# robo1.net
KiCad netlist of a schematic drawn in EAGLE
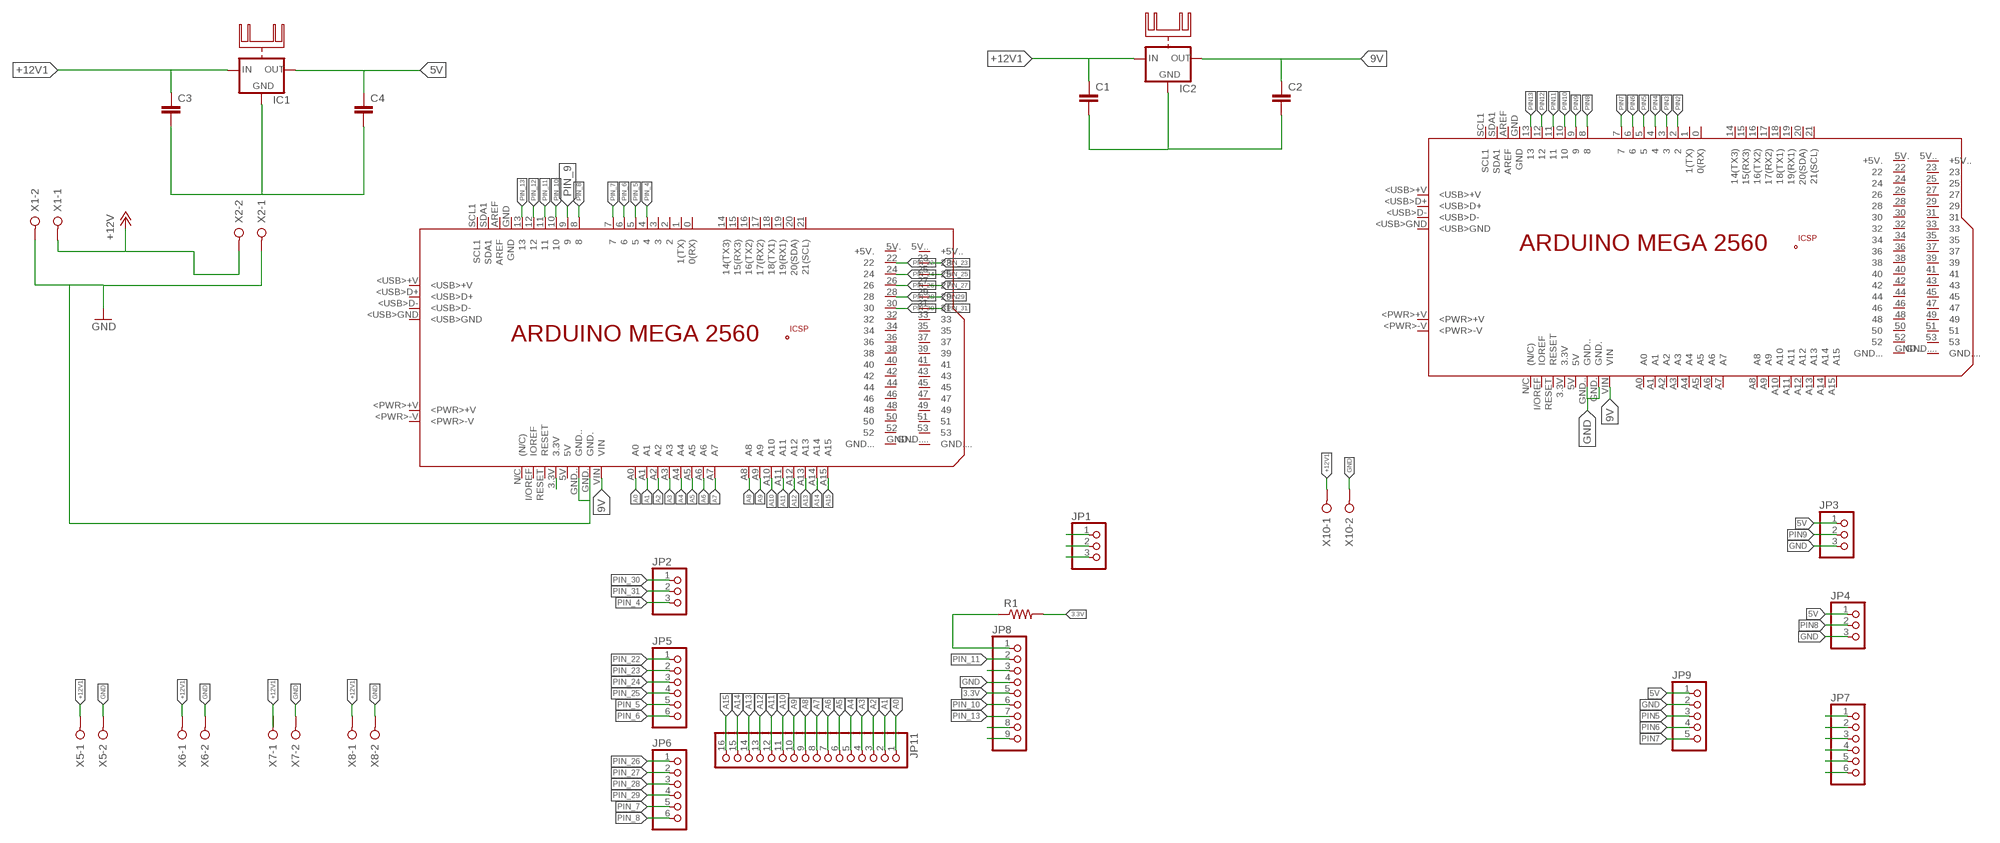
[diagram p0: schematic, sheet 1]

(export (version "E")
  (design (tool "Eeschema 10.0.6"))
  (components
    (comp (ref "C1")
      (value "C5/2.5")
      (footprint "eagle-import:C5B2.5")
      (libsource (lib "eagle-import") (part "C5/2.5"))
    )
    (comp (ref "C2")
      (value "C5/2.5")
      (footprint "eagle-import:C5B2.5")
      (libsource (lib "eagle-import") (part "C5/2.5"))
    )
    (comp (ref "C3")
      (value "C5/2.5")
      (footprint "eagle-import:C5B2.5")
      (libsource (lib "eagle-import") (part "C5/2.5"))
    )
    (comp (ref "C4")
      (value "C5/2.5")
      (footprint "eagle-import:C5B2.5")
      (libsource (lib "eagle-import") (part "C5/2.5"))
    )
    (comp (ref "IC1")
      (value "78XXH")
      (footprint "eagle-import:78XXH")
      (libsource (lib "eagle-import") (part "78XXH"))
    )
    (comp (ref "IC2")
      (value "78XXH")
      (footprint "eagle-import:78XXH")
      (libsource (lib "eagle-import") (part "78XXH"))
    )
    (comp (ref "JP1")
      (value "PINHD-1X3")
      (footprint "eagle-import:1X03")
      (libsource (lib "eagle-import") (part "PINHD-1X3"))
    )
    (comp (ref "JP2")
      (value "PINHD-1X3")
      (footprint "eagle-import:1X03")
      (libsource (lib "eagle-import") (part "PINHD-1X3"))
    )
    (comp (ref "JP3")
      (value "PINHD-1X3")
      (footprint "eagle-import:1X03")
      (libsource (lib "eagle-import") (part "PINHD-1X3"))
    )
    (comp (ref "JP4")
      (value "PINHD-1X3")
      (footprint "eagle-import:1X03")
      (libsource (lib "eagle-import") (part "PINHD-1X3"))
    )
    (comp (ref "JP5")
      (value "PINHD-1X6")
      (footprint "eagle-import:1X06")
      (libsource (lib "eagle-import") (part "PINHD-1X6"))
    )
    (comp (ref "JP6")
      (value "PINHD-1X6")
      (footprint "eagle-import:1X06")
      (libsource (lib "eagle-import") (part "PINHD-1X6"))
    )
    (comp (ref "JP7")
      (value "PINHD-1X6")
      (footprint "eagle-import:1X06")
      (libsource (lib "eagle-import") (part "PINHD-1X6"))
    )
    (comp (ref "JP8")
      (value "PINHD-1X9")
      (footprint "eagle-import:1X09")
      (libsource (lib "eagle-import") (part "PINHD-1X9"))
    )
    (comp (ref "JP9")
      (value "PINHD-1X5")
      (footprint "eagle-import:1X05")
      (libsource (lib "eagle-import") (part "PINHD-1X5"))
    )
    (comp (ref "JP11")
      (value "PINHD-1X16")
      (footprint "eagle-import:1X16")
      (libsource (lib "eagle-import") (part "PINHD-1X16"))
    )
    (comp (ref "MEGA1")
      (value "ARDUINO_MEGA2560")
      (footprint "eagle-import:ARDUINO_MEGA2560")
      (libsource (lib "eagle-import") (part "ARDUINO_MEGA2560"))
    )
    (comp (ref "MEGA2")
      (value "ARDUINO_MEGA2560")
      (footprint "eagle-import:ARDUINO_MEGA2560")
      (libsource (lib "eagle-import") (part "ARDUINO_MEGA2560"))
    )
    (comp (ref "R1")
      (value "R-US_0207/10")
      (footprint "eagle-import:0207_10")
      (libsource (lib "eagle-import") (part "R-US_0207/10"))
    )
    (comp (ref "X1")
      (value "W237-02P")
      (footprint "eagle-import:W237-132")
      (libsource (lib "eagle-import") (part "W237-02P"))
    )
    (comp (ref "X2")
      (value "W237-02P")
      (footprint "eagle-import:W237-132")
      (libsource (lib "eagle-import") (part "W237-02P"))
    )
    (comp (ref "X5")
      (value "W237-02P")
      (footprint "eagle-import:W237-132")
      (libsource (lib "eagle-import") (part "W237-02P"))
    )
    (comp (ref "X6")
      (value "W237-02P")
      (footprint "eagle-import:W237-132")
      (libsource (lib "eagle-import") (part "W237-02P"))
    )
    (comp (ref "X7")
      (value "W237-02P")
      (footprint "eagle-import:W237-132")
      (libsource (lib "eagle-import") (part "W237-02P"))
    )
    (comp (ref "X8")
      (value "W237-02P")
      (footprint "eagle-import:W237-132")
      (libsource (lib "eagle-import") (part "W237-02P"))
    )
    (comp (ref "X10")
      (value "W237-02P")
      (footprint "eagle-import:W237-132")
      (libsource (lib "eagle-import") (part "W237-02P"))
    )
  )
  (nets
    (net (code "1") (name "+12V") (class "Default")
      (node (ref "X1") (pin "1") (pinfunction "KL_1") (pintype "passive"))
      (node (ref "X2") (pin "2") (pinfunction "KL_2") (pintype "passive"))
    )
    (net (code "2") (name "+12V1") (class "Default")
      (node (ref "C1") (pin "1") (pinfunction "1_1") (pintype "passive"))
      (node (ref "C3") (pin "1") (pinfunction "1_1") (pintype "passive"))
      (node (ref "IC1") (pin "IN") (pinfunction "IN_IN") (pintype "input"))
      (node (ref "IC2") (pin "IN") (pinfunction "IN_IN") (pintype "input"))
      (node (ref "X10") (pin "1") (pinfunction "KL_1") (pintype "passive"))
      (node (ref "X5") (pin "1") (pinfunction "KL_1") (pintype "passive"))
      (node (ref "X6") (pin "1") (pinfunction "KL_1") (pintype "passive"))
      (node (ref "X8") (pin "1") (pinfunction "KL_1") (pintype "passive"))
    )
    (net (code "3") (name "3.3V") (class "Default")
      (node (ref "JP8") (pin "5") (pinfunction "5_5") (pintype "passive"))
      (node (ref "MEGA1") (pin "3.3V") (pinfunction "3.3V_3.3V") (pintype "bidirectional"))
      (node (ref "R1") (pin "2") (pinfunction "2_2") (pintype "passive"))
    )
    (net (code "4") (name "5V") (class "Default")
      (node (ref "C4") (pin "1") (pinfunction "1_1") (pintype "passive"))
      (node (ref "IC1") (pin "OUT") (pinfunction "OUT_OUT") (pintype "passive"))
      (node (ref "JP3") (pin "1") (pinfunction "1_1") (pintype "passive"))
      (node (ref "JP4") (pin "1") (pinfunction "1_1") (pintype "passive"))
      (node (ref "JP9") (pin "1") (pinfunction "1_1") (pintype "passive"))
    )
    (net (code "5") (name "9V") (class "Default")
      (node (ref "C2") (pin "1") (pinfunction "1_1") (pintype "passive"))
      (node (ref "IC2") (pin "OUT") (pinfunction "OUT_OUT") (pintype "passive"))
      (node (ref "MEGA1") (pin "VIN") (pinfunction "VIN_VIN") (pintype "bidirectional"))
      (node (ref "MEGA2") (pin "VIN") (pinfunction "VIN_VIN") (pintype "bidirectional"))
    )
    (net (code "6") (name "A0") (class "Default")
      (node (ref "JP11") (pin "1") (pinfunction "1_1") (pintype "passive"))
      (node (ref "MEGA1") (pin "A0") (pinfunction "A0_A0") (pintype "bidirectional"))
    )
    (net (code "7") (name "A1") (class "Default")
      (node (ref "JP11") (pin "2") (pinfunction "2_2") (pintype "passive"))
      (node (ref "MEGA1") (pin "A1") (pinfunction "A1_A1") (pintype "bidirectional"))
    )
    (net (code "8") (name "A2") (class "Default")
      (node (ref "JP11") (pin "3") (pinfunction "3_3") (pintype "passive"))
      (node (ref "MEGA1") (pin "A2") (pinfunction "A2_A2") (pintype "bidirectional"))
    )
    (net (code "9") (name "A3") (class "Default")
      (node (ref "JP11") (pin "4") (pinfunction "4_4") (pintype "passive"))
      (node (ref "MEGA1") (pin "A3") (pinfunction "A3_A3") (pintype "bidirectional"))
    )
    (net (code "10") (name "A4") (class "Default")
      (node (ref "JP11") (pin "5") (pinfunction "5_5") (pintype "passive"))
      (node (ref "MEGA1") (pin "A4") (pinfunction "A4_A4") (pintype "bidirectional"))
    )
    (net (code "11") (name "A5") (class "Default")
      (node (ref "JP11") (pin "6") (pinfunction "6_6") (pintype "passive"))
      (node (ref "MEGA1") (pin "A5") (pinfunction "A5_A5") (pintype "bidirectional"))
    )
    (net (code "12") (name "A6") (class "Default")
      (node (ref "JP11") (pin "7") (pinfunction "7_7") (pintype "passive"))
      (node (ref "MEGA1") (pin "A6") (pinfunction "A6_A6") (pintype "bidirectional"))
    )
    (net (code "13") (name "A7") (class "Default")
      (node (ref "JP11") (pin "8") (pinfunction "8_8") (pintype "passive"))
      (node (ref "MEGA1") (pin "A7") (pinfunction "A7_A7") (pintype "bidirectional"))
    )
    (net (code "14") (name "A8") (class "Default")
      (node (ref "JP11") (pin "9") (pinfunction "9_9") (pintype "passive"))
      (node (ref "MEGA1") (pin "A8") (pinfunction "A8_A8") (pintype "bidirectional"))
    )
    (net (code "15") (name "A9") (class "Default")
      (node (ref "JP11") (pin "10") (pinfunction "10_10") (pintype "passive"))
      (node (ref "MEGA1") (pin "A9") (pinfunction "A9_A9") (pintype "bidirectional"))
    )
    (net (code "16") (name "A10") (class "Default")
      (node (ref "JP11") (pin "11") (pinfunction "11_11") (pintype "passive"))
      (node (ref "MEGA1") (pin "A10") (pinfunction "A10_A10") (pintype "bidirectional"))
    )
    (net (code "17") (name "A11") (class "Default")
      (node (ref "JP11") (pin "12") (pinfunction "12_12") (pintype "passive"))
      (node (ref "MEGA1") (pin "A11") (pinfunction "A11_A11") (pintype "bidirectional"))
    )
    (net (code "18") (name "A12") (class "Default")
      (node (ref "JP11") (pin "13") (pinfunction "13_13") (pintype "passive"))
      (node (ref "MEGA1") (pin "A12") (pinfunction "A12_A12") (pintype "bidirectional"))
    )
    (net (code "19") (name "A13") (class "Default")
      (node (ref "JP11") (pin "14") (pinfunction "14_14") (pintype "passive"))
      (node (ref "MEGA1") (pin "A13") (pinfunction "A13_A13") (pintype "bidirectional"))
    )
    (net (code "20") (name "A14") (class "Default")
      (node (ref "JP11") (pin "15") (pinfunction "15_15") (pintype "passive"))
      (node (ref "MEGA1") (pin "A14") (pinfunction "A14_A14") (pintype "bidirectional"))
    )
    (net (code "21") (name "A15") (class "Default")
      (node (ref "JP11") (pin "16") (pinfunction "16_16") (pintype "passive"))
      (node (ref "MEGA1") (pin "A15") (pinfunction "A15_A15") (pintype "bidirectional"))
    )
    (net (code "22") (name "GND") (class "Default")
      (node (ref "C1") (pin "2") (pinfunction "2_2") (pintype "passive"))
      (node (ref "C2") (pin "2") (pinfunction "2_2") (pintype "passive"))
      (node (ref "C3") (pin "2") (pinfunction "2_2") (pintype "passive"))
      (node (ref "C4") (pin "2") (pinfunction "2_2") (pintype "passive"))
      (node (ref "IC1") (pin "GND") (pinfunction "GND_GND") (pintype "input"))
      (node (ref "IC2") (pin "GND") (pinfunction "GND_GND") (pintype "input"))
      (node (ref "JP1") (pin "1") (pinfunction "1_1") (pintype "passive"))
      (node (ref "JP3") (pin "3") (pinfunction "3_3") (pintype "passive"))
      (node (ref "JP4") (pin "3") (pinfunction "3_3") (pintype "passive"))
      (node (ref "JP8") (pin "4") (pinfunction "4_4") (pintype "passive"))
      (node (ref "JP9") (pin "2") (pinfunction "2_2") (pintype "passive"))
      (node (ref "MEGA1") (pin "GND.") (pinfunction "GND._GND.") (pintype "bidirectional"))
      (node (ref "MEGA1") (pin "GND..") (pinfunction "GND.._GND..") (pintype "bidirectional"))
      (node (ref "MEGA2") (pin "GND.") (pinfunction "GND._GND.") (pintype "bidirectional"))
      (node (ref "MEGA2") (pin "GND..") (pinfunction "GND.._GND..") (pintype "bidirectional"))
      (node (ref "X1") (pin "2") (pinfunction "KL_2") (pintype "passive"))
      (node (ref "X10") (pin "2") (pinfunction "KL_2") (pintype "passive"))
      (node (ref "X2") (pin "1") (pinfunction "KL_1") (pintype "passive"))
      (node (ref "X5") (pin "2") (pinfunction "KL_2") (pintype "passive"))
      (node (ref "X6") (pin "2") (pinfunction "KL_2") (pintype "passive"))
      (node (ref "X7") (pin "2") (pinfunction "KL_2") (pintype "passive"))
      (node (ref "X8") (pin "2") (pinfunction "KL_2") (pintype "passive"))
    )
    (net (code "23") (name "PIN2") (class "Default")
      (node (ref "JP7") (pin "1") (pinfunction "1_1") (pintype "passive"))
      (node (ref "MEGA2") (pin "2") (pinfunction "2_2") (pintype "bidirectional"))
    )
    (net (code "24") (name "PIN3") (class "Default")
      (node (ref "JP7") (pin "2") (pinfunction "2_2") (pintype "passive"))
      (node (ref "MEGA2") (pin "3") (pinfunction "3_3") (pintype "bidirectional"))
    )
    (net (code "25") (name "PIN4") (class "Default")
      (node (ref "MEGA2") (pin "4") (pinfunction "4_4") (pintype "bidirectional"))
    )
    (net (code "26") (name "PIN5") (class "Default")
      (node (ref "JP9") (pin "3") (pinfunction "3_3") (pintype "passive"))
      (node (ref "MEGA2") (pin "5") (pinfunction "5_5") (pintype "bidirectional"))
    )
    (net (code "27") (name "PIN6") (class "Default")
      (node (ref "JP9") (pin "4") (pinfunction "4_4") (pintype "passive"))
      (node (ref "MEGA2") (pin "6") (pinfunction "6_6") (pintype "bidirectional"))
    )
    (net (code "28") (name "PIN7") (class "Default")
      (node (ref "JP9") (pin "5") (pinfunction "5_5") (pintype "passive"))
      (node (ref "MEGA2") (pin "7") (pinfunction "7_7") (pintype "bidirectional"))
    )
    (net (code "29") (name "PIN8") (class "Default")
      (node (ref "JP4") (pin "2") (pinfunction "2_2") (pintype "passive"))
      (node (ref "MEGA2") (pin "8") (pinfunction "8_8") (pintype "bidirectional"))
    )
    (net (code "30") (name "PIN9") (class "Default")
      (node (ref "JP3") (pin "2") (pinfunction "2_2") (pintype "passive"))
      (node (ref "MEGA2") (pin "9") (pinfunction "9_9") (pintype "bidirectional"))
    )
    (net (code "31") (name "PIN10") (class "Default")
      (node (ref "JP7") (pin "3") (pinfunction "3_3") (pintype "passive"))
      (node (ref "MEGA2") (pin "10") (pinfunction "10_10") (pintype "bidirectional"))
    )
    (net (code "32") (name "PIN11") (class "Default")
      (node (ref "JP7") (pin "4") (pinfunction "4_4") (pintype "passive"))
      (node (ref "MEGA2") (pin "11") (pinfunction "11_11") (pintype "bidirectional"))
    )
    (net (code "33") (name "PIN12") (class "Default")
      (node (ref "JP7") (pin "5") (pinfunction "5_5") (pintype "passive"))
      (node (ref "MEGA2") (pin "12") (pinfunction "12_12") (pintype "bidirectional"))
    )
    (net (code "34") (name "PIN13") (class "Default")
      (node (ref "JP7") (pin "6") (pinfunction "6_6") (pintype "passive"))
      (node (ref "MEGA2") (pin "13") (pinfunction "13_13") (pintype "bidirectional"))
    )
    (net (code "36") (name "PIN_4") (class "Default")
      (node (ref "JP2") (pin "3") (pinfunction "3_3") (pintype "passive"))
      (node (ref "MEGA1") (pin "4") (pinfunction "4_4") (pintype "bidirectional"))
    )
    (net (code "37") (name "PIN_5") (class "Default")
      (node (ref "JP5") (pin "5") (pinfunction "5_5") (pintype "passive"))
      (node (ref "MEGA1") (pin "5") (pinfunction "5_5") (pintype "bidirectional"))
    )
    (net (code "38") (name "PIN_6") (class "Default")
      (node (ref "JP5") (pin "6") (pinfunction "6_6") (pintype "passive"))
      (node (ref "MEGA1") (pin "6") (pinfunction "6_6") (pintype "bidirectional"))
    )
    (net (code "39") (name "PIN_7") (class "Default")
      (node (ref "JP6") (pin "5") (pinfunction "5_5") (pintype "passive"))
      (node (ref "MEGA1") (pin "7") (pinfunction "7_7") (pintype "bidirectional"))
    )
    (net (code "40") (name "PIN_8") (class "Default")
      (node (ref "JP6") (pin "6") (pinfunction "6_6") (pintype "passive"))
      (node (ref "MEGA1") (pin "8") (pinfunction "8_8") (pintype "bidirectional"))
    )
    (net (code "41") (name "PIN_9") (class "Default")
      (node (ref "JP1") (pin "3") (pinfunction "3_3") (pintype "passive"))
      (node (ref "MEGA1") (pin "9") (pinfunction "9_9") (pintype "bidirectional"))
    )
    (net (code "42") (name "PIN_10") (class "Default")
      (node (ref "JP8") (pin "6") (pinfunction "6_6") (pintype "passive"))
      (node (ref "MEGA1") (pin "10") (pinfunction "10_10") (pintype "bidirectional"))
    )
    (net (code "43") (name "PIN_11") (class "Default")
      (node (ref "JP8") (pin "2") (pinfunction "2_2") (pintype "passive"))
      (node (ref "MEGA1") (pin "11") (pinfunction "11_11") (pintype "bidirectional"))
    )
    (net (code "44") (name "PIN_12") (class "Default")
      (node (ref "JP8") (pin "1") (pinfunction "1_1") (pintype "passive"))
      (node (ref "MEGA1") (pin "12") (pinfunction "12_12") (pintype "bidirectional"))
      (node (ref "R1") (pin "1") (pinfunction "1_1") (pintype "passive"))
    )
    (net (code "45") (name "PIN_13") (class "Default")
      (node (ref "JP8") (pin "7") (pinfunction "7_7") (pintype "passive"))
      (node (ref "MEGA1") (pin "13") (pinfunction "13_13") (pintype "bidirectional"))
    )
    (net (code "46") (name "PIN_22") (class "Default")
      (node (ref "JP5") (pin "1") (pinfunction "1_1") (pintype "passive"))
      (node (ref "MEGA1") (pin "22") (pinfunction "22_22") (pintype "bidirectional"))
    )
    (net (code "47") (name "PIN_23") (class "Default")
      (node (ref "JP5") (pin "2") (pinfunction "2_2") (pintype "passive"))
    )
    (net (code "48") (name "PIN_24") (class "Default")
      (node (ref "JP5") (pin "3") (pinfunction "3_3") (pintype "passive"))
      (node (ref "MEGA1") (pin "24") (pinfunction "24_24") (pintype "bidirectional"))
    )
    (net (code "49") (name "PIN_25") (class "Default")
      (node (ref "JP5") (pin "4") (pinfunction "4_4") (pintype "passive"))
    )
    (net (code "50") (name "PIN_26") (class "Default")
      (node (ref "JP6") (pin "1") (pinfunction "1_1") (pintype "passive"))
      (node (ref "MEGA1") (pin "26") (pinfunction "26_26") (pintype "bidirectional"))
    )
    (net (code "51") (name "PIN_27") (class "Default")
      (node (ref "JP6") (pin "2") (pinfunction "2_2") (pintype "passive"))
    )
    (net (code "52") (name "PIN_28") (class "Default")
      (node (ref "JP6") (pin "3") (pinfunction "3_3") (pintype "passive"))
      (node (ref "MEGA1") (pin "28") (pinfunction "28_28") (pintype "bidirectional"))
    )
    (net (code "53") (name "PIN_29") (class "Default")
      (node (ref "JP6") (pin "4") (pinfunction "4_4") (pintype "passive"))
    )
    (net (code "54") (name "PIN_30") (class "Default")
      (node (ref "JP2") (pin "1") (pinfunction "1_1") (pintype "passive"))
      (node (ref "MEGA1") (pin "30") (pinfunction "30_30") (pintype "bidirectional"))
    )
    (net (code "55") (name "PIN_31") (class "Default")
      (node (ref "JP2") (pin "2") (pinfunction "2_2") (pintype "passive"))
    )
    (net (code "56") (name "unconnected-(JP1-Pad2)") (class "Default")
      (node (ref "JP1") (pin "2") (pinfunction "2_2") (pintype "passive"))
    )
    (net (code "57") (name "unconnected-(JP8-Pad3)") (class "Default")
      (node (ref "JP8") (pin "3") (pinfunction "3_3") (pintype "passive"))
    )
    (net (code "58") (name "unconnected-(JP8-Pad8)") (class "Default")
      (node (ref "JP8") (pin "8") (pinfunction "8_8") (pintype "passive"))
    )
    (net (code "59") (name "unconnected-(JP8-Pad9)") (class "Default")
      (node (ref "JP8") (pin "9") (pinfunction "9_9") (pintype "passive"))
    )
    (net (code "60") (name "unconnected-(MEGA1-(N{slash}C)-PadN{slash}C)") (class "Default")
      (node (ref "MEGA1") (pin "N/C") (pinfunction "(N/C)_N/C") (pintype "bidirectional"))
    )
    (net (code "61") (name "unconnected-(MEGA1-+5V.-Pad5V.)") (class "Default")
      (node (ref "MEGA1") (pin "5V.") (pinfunction "+5V._5V.") (pintype "bidirectional"))
    )
    (net (code "62") (name "unconnected-(MEGA1-+5V..-Pad5V..)") (class "Default")
      (node (ref "MEGA1") (pin "5V..") (pinfunction "+5V.._5V..") (pintype "bidirectional"))
    )
    (net (code "63") (name "unconnected-(MEGA1-0(RX)-Pad0)") (class "Default")
      (node (ref "MEGA1") (pin "0") (pinfunction "0(RX)_0") (pintype "bidirectional"))
    )
    (net (code "64") (name "unconnected-(MEGA1-1(TX)-Pad1)") (class "Default")
      (node (ref "MEGA1") (pin "1") (pinfunction "1(TX)_1") (pintype "bidirectional"))
    )
    (net (code "65") (name "unconnected-(MEGA1-14(TX3)-Pad14)") (class "Default")
      (node (ref "MEGA1") (pin "14") (pinfunction "14(TX3)_14") (pintype "bidirectional"))
    )
    (net (code "66") (name "unconnected-(MEGA1-15(RX3)-Pad15)") (class "Default")
      (node (ref "MEGA1") (pin "15") (pinfunction "15(RX3)_15") (pintype "bidirectional"))
    )
    (net (code "67") (name "unconnected-(MEGA1-16(TX2)-Pad16)") (class "Default")
      (node (ref "MEGA1") (pin "16") (pinfunction "16(TX2)_16") (pintype "bidirectional"))
    )
    (net (code "68") (name "unconnected-(MEGA1-17(RX2)-Pad17)") (class "Default")
      (node (ref "MEGA1") (pin "17") (pinfunction "17(RX2)_17") (pintype "bidirectional"))
    )
    (net (code "69") (name "unconnected-(MEGA1-18(TX1)-Pad18)") (class "Default")
      (node (ref "MEGA1") (pin "18") (pinfunction "18(TX1)_18") (pintype "bidirectional"))
    )
    (net (code "70") (name "unconnected-(MEGA1-19(RX1)-Pad19)") (class "Default")
      (node (ref "MEGA1") (pin "19") (pinfunction "19(RX1)_19") (pintype "bidirectional"))
    )
    (net (code "71") (name "unconnected-(MEGA1-20(SDA)-Pad20)") (class "Default")
      (node (ref "MEGA1") (pin "20") (pinfunction "20(SDA)_20") (pintype "bidirectional"))
    )
    (net (code "72") (name "unconnected-(MEGA1-21(SCL)-Pad21)") (class "Default")
      (node (ref "MEGA1") (pin "21") (pinfunction "21(SCL)_21") (pintype "bidirectional"))
    )
    (net (code "73") (name "unconnected-(MEGA1-IOREF-PadI{slash}OREF)") (class "Default")
      (node (ref "MEGA1") (pin "I/OREF") (pinfunction "IOREF_I/OREF") (pintype "bidirectional"))
    )
    (net (code "74") (name "unconnected-(MEGA1-Pad+5V_)") (class "Default")
      (node (ref "MEGA1") (pin "+5V_") (pinfunction "+5V__+5V_") (pintype "bidirectional"))
    )
    (net (code "75") (name "unconnected-(MEGA1-Pad2)") (class "Default")
      (node (ref "MEGA1") (pin "2") (pinfunction "2_2") (pintype "bidirectional"))
    )
    (net (code "76") (name "unconnected-(MEGA1-Pad3)") (class "Default")
      (node (ref "MEGA1") (pin "3") (pinfunction "3_3") (pintype "bidirectional"))
    )
    (net (code "77") (name "unconnected-(MEGA1-Pad5V)") (class "Default")
      (node (ref "MEGA1") (pin "5V") (pinfunction "5V_5V") (pintype "bidirectional"))
    )
    (net (code "78") (name "unconnected-(MEGA1-Pad23)") (class "Default")
      (node (ref "MEGA1") (pin "23") (pinfunction "23_23") (pintype "bidirectional"))
    )
    (net (code "79") (name "unconnected-(MEGA1-Pad25)") (class "Default")
      (node (ref "MEGA1") (pin "25") (pinfunction "25_25") (pintype "bidirectional"))
    )
    (net (code "80") (name "unconnected-(MEGA1-Pad27)") (class "Default")
      (node (ref "MEGA1") (pin "27") (pinfunction "27_27") (pintype "bidirectional"))
    )
    (net (code "81") (name "unconnected-(MEGA1-Pad29)") (class "Default")
      (node (ref "MEGA1") (pin "29") (pinfunction "29_29") (pintype "bidirectional"))
    )
    (net (code "82") (name "unconnected-(MEGA1-Pad31)") (class "Default")
      (node (ref "MEGA1") (pin "31") (pinfunction "31_31") (pintype "bidirectional"))
    )
    (net (code "83") (name "unconnected-(MEGA1-Pad32)") (class "Default")
      (node (ref "MEGA1") (pin "32") (pinfunction "32_32") (pintype "bidirectional"))
    )
    (net (code "84") (name "unconnected-(MEGA1-Pad33)") (class "Default")
      (node (ref "MEGA1") (pin "33") (pinfunction "33_33") (pintype "bidirectional"))
    )
    (net (code "85") (name "unconnected-(MEGA1-Pad34)") (class "Default")
      (node (ref "MEGA1") (pin "34") (pinfunction "34_34") (pintype "bidirectional"))
    )
    (net (code "86") (name "unconnected-(MEGA1-Pad35)") (class "Default")
      (node (ref "MEGA1") (pin "35") (pinfunction "35_35") (pintype "bidirectional"))
    )
    (net (code "87") (name "unconnected-(MEGA1-Pad36)") (class "Default")
      (node (ref "MEGA1") (pin "36") (pinfunction "36_36") (pintype "bidirectional"))
    )
    (net (code "88") (name "unconnected-(MEGA1-Pad37)") (class "Default")
      (node (ref "MEGA1") (pin "37") (pinfunction "37_37") (pintype "bidirectional"))
    )
    (net (code "89") (name "unconnected-(MEGA1-Pad38)") (class "Default")
      (node (ref "MEGA1") (pin "38") (pinfunction "38_38") (pintype "bidirectional"))
    )
    (net (code "90") (name "unconnected-(MEGA1-Pad39)") (class "Default")
      (node (ref "MEGA1") (pin "39") (pinfunction "39_39") (pintype "bidirectional"))
    )
    (net (code "91") (name "unconnected-(MEGA1-Pad40)") (class "Default")
      (node (ref "MEGA1") (pin "40") (pinfunction "40_40") (pintype "bidirectional"))
    )
    (net (code "92") (name "unconnected-(MEGA1-Pad41)") (class "Default")
      (node (ref "MEGA1") (pin "41") (pinfunction "41_41") (pintype "bidirectional"))
    )
    (net (code "93") (name "unconnected-(MEGA1-Pad42)") (class "Default")
      (node (ref "MEGA1") (pin "42") (pinfunction "42_42") (pintype "bidirectional"))
    )
    (net (code "94") (name "unconnected-(MEGA1-Pad43)") (class "Default")
      (node (ref "MEGA1") (pin "43") (pinfunction "43_43") (pintype "bidirectional"))
    )
    (net (code "95") (name "unconnected-(MEGA1-Pad44)") (class "Default")
      (node (ref "MEGA1") (pin "44") (pinfunction "44_44") (pintype "bidirectional"))
    )
    (net (code "96") (name "unconnected-(MEGA1-Pad45)") (class "Default")
      (node (ref "MEGA1") (pin "45") (pinfunction "45_45") (pintype "bidirectional"))
    )
    (net (code "97") (name "unconnected-(MEGA1-Pad46)") (class "Default")
      (node (ref "MEGA1") (pin "46") (pinfunction "46_46") (pintype "bidirectional"))
    )
    (net (code "98") (name "unconnected-(MEGA1-Pad47)") (class "Default")
      (node (ref "MEGA1") (pin "47") (pinfunction "47_47") (pintype "bidirectional"))
    )
    (net (code "99") (name "unconnected-(MEGA1-Pad48)") (class "Default")
      (node (ref "MEGA1") (pin "48") (pinfunction "48_48") (pintype "bidirectional"))
    )
    (net (code "100") (name "unconnected-(MEGA1-Pad49)") (class "Default")
      (node (ref "MEGA1") (pin "49") (pinfunction "49_49") (pintype "bidirectional"))
    )
    (net (code "101") (name "unconnected-(MEGA1-Pad50)") (class "Default")
      (node (ref "MEGA1") (pin "50") (pinfunction "50_50") (pintype "bidirectional"))
    )
    (net (code "102") (name "unconnected-(MEGA1-Pad51)") (class "Default")
      (node (ref "MEGA1") (pin "51") (pinfunction "51_51") (pintype "bidirectional"))
    )
    (net (code "103") (name "unconnected-(MEGA1-Pad52)") (class "Default")
      (node (ref "MEGA1") (pin "52") (pinfunction "52_52") (pintype "bidirectional"))
    )
    (net (code "104") (name "unconnected-(MEGA1-Pad53)") (class "Default")
      (node (ref "MEGA1") (pin "53") (pinfunction "53_53") (pintype "bidirectional"))
    )
    (net (code "105") (name "unconnected-(MEGA1-Pad<PWR>+V)") (class "Default")
      (node (ref "MEGA1") (pin "<PWR>+V") (pinfunction "<PWR>+V_<PWR>+V") (pintype "no_connect"))
    )
    (net (code "106") (name "unconnected-(MEGA1-Pad<PWR>-V)") (class "Default")
      (node (ref "MEGA1") (pin "<PWR>-V") (pinfunction "<PWR>-V_<PWR>-V") (pintype "no_connect"))
    )
    (net (code "107") (name "unconnected-(MEGA1-Pad<USB>+V)") (class "Default")
      (node (ref "MEGA1") (pin "<USB>+V") (pinfunction "<USB>+V_<USB>+V") (pintype "no_connect"))
    )
    (net (code "108") (name "unconnected-(MEGA1-Pad<USB>D+)") (class "Default")
      (node (ref "MEGA1") (pin "<USB>D+") (pinfunction "<USB>D+_<USB>D+") (pintype "no_connect"))
    )
    (net (code "109") (name "unconnected-(MEGA1-Pad<USB>D-)") (class "Default")
      (node (ref "MEGA1") (pin "<USB>D-") (pinfunction "<USB>D-_<USB>D-") (pintype "no_connect"))
    )
    (net (code "110") (name "unconnected-(MEGA1-Pad<USB>GND)") (class "Default")
      (node (ref "MEGA1") (pin "<USB>GND") (pinfunction "<USB>GND_<USB>GND") (pintype "no_connect"))
    )
    (net (code "111") (name "unconnected-(MEGA1-PadAREF)") (class "Default")
      (node (ref "MEGA1") (pin "AREF") (pinfunction "AREF_AREF") (pintype "bidirectional"))
    )
    (net (code "112") (name "unconnected-(MEGA1-PadGND)") (class "Default")
      (node (ref "MEGA1") (pin "GND") (pinfunction "GND_GND") (pintype "bidirectional"))
    )
    (net (code "113") (name "unconnected-(MEGA1-PadGND...)") (class "Default")
      (node (ref "MEGA1") (pin "GND...") (pinfunction "GND..._GND...") (pintype "bidirectional"))
    )
    (net (code "114") (name "unconnected-(MEGA1-PadGND....)") (class "Default")
      (node (ref "MEGA1") (pin "GND....") (pinfunction "GND...._GND....") (pintype "bidirectional"))
    )
    (net (code "115") (name "unconnected-(MEGA1-PadGND__)") (class "Default")
      (node (ref "MEGA1") (pin "GND__") (pinfunction "GND___GND__") (pintype "bidirectional"))
    )
    (net (code "116") (name "unconnected-(MEGA1-PadMISO)") (class "Default")
      (node (ref "MEGA1") (pin "MISO") (pinfunction "MISO_MISO") (pintype "bidirectional"))
    )
    (net (code "117") (name "unconnected-(MEGA1-PadMOSI)") (class "Default")
      (node (ref "MEGA1") (pin "MOSI") (pinfunction "MOSI_MOSI") (pintype "bidirectional"))
    )
    (net (code "118") (name "unconnected-(MEGA1-PadRESET)") (class "Default")
      (node (ref "MEGA1") (pin "RESET") (pinfunction "RESET_RESET") (pintype "bidirectional"))
    )
    (net (code "119") (name "unconnected-(MEGA1-PadRESET.)") (class "Default")
      (node (ref "MEGA1") (pin "RESET.") (pinfunction "RESET._RESET.") (pintype "bidirectional"))
    )
    (net (code "120") (name "unconnected-(MEGA1-PadSCK)") (class "Default")
      (node (ref "MEGA1") (pin "SCK") (pinfunction "SCK_SCK") (pintype "bidirectional"))
    )
    (net (code "121") (name "unconnected-(MEGA1-PadSCL1)") (class "Default")
      (node (ref "MEGA1") (pin "SCL1") (pinfunction "SCL1_SCL1") (pintype "bidirectional"))
    )
    (net (code "122") (name "unconnected-(MEGA1-PadSDA1)") (class "Default")
      (node (ref "MEGA1") (pin "SDA1") (pinfunction "SDA1_SDA1") (pintype "bidirectional"))
    )
    (net (code "123") (name "unconnected-(MEGA2-(N{slash}C)-PadN{slash}C)") (class "Default")
      (node (ref "MEGA2") (pin "N/C") (pinfunction "(N/C)_N/C") (pintype "bidirectional"))
    )
    (net (code "124") (name "unconnected-(MEGA2-+5V.-Pad5V.)") (class "Default")
      (node (ref "MEGA2") (pin "5V.") (pinfunction "+5V._5V.") (pintype "bidirectional"))
    )
    (net (code "125") (name "unconnected-(MEGA2-+5V..-Pad5V..)") (class "Default")
      (node (ref "MEGA2") (pin "5V..") (pinfunction "+5V.._5V..") (pintype "bidirectional"))
    )
    (net (code "126") (name "unconnected-(MEGA2-0(RX)-Pad0)") (class "Default")
      (node (ref "MEGA2") (pin "0") (pinfunction "0(RX)_0") (pintype "bidirectional"))
    )
    (net (code "127") (name "unconnected-(MEGA2-1(TX)-Pad1)") (class "Default")
      (node (ref "MEGA2") (pin "1") (pinfunction "1(TX)_1") (pintype "bidirectional"))
    )
    (net (code "128") (name "unconnected-(MEGA2-14(TX3)-Pad14)") (class "Default")
      (node (ref "MEGA2") (pin "14") (pinfunction "14(TX3)_14") (pintype "bidirectional"))
    )
    (net (code "129") (name "unconnected-(MEGA2-15(RX3)-Pad15)") (class "Default")
      (node (ref "MEGA2") (pin "15") (pinfunction "15(RX3)_15") (pintype "bidirectional"))
    )
    (net (code "130") (name "unconnected-(MEGA2-16(TX2)-Pad16)") (class "Default")
      (node (ref "MEGA2") (pin "16") (pinfunction "16(TX2)_16") (pintype "bidirectional"))
    )
    (net (code "131") (name "unconnected-(MEGA2-17(RX2)-Pad17)") (class "Default")
      (node (ref "MEGA2") (pin "17") (pinfunction "17(RX2)_17") (pintype "bidirectional"))
    )
    (net (code "132") (name "unconnected-(MEGA2-18(TX1)-Pad18)") (class "Default")
      (node (ref "MEGA2") (pin "18") (pinfunction "18(TX1)_18") (pintype "bidirectional"))
    )
    (net (code "133") (name "unconnected-(MEGA2-19(RX1)-Pad19)") (class "Default")
      (node (ref "MEGA2") (pin "19") (pinfunction "19(RX1)_19") (pintype "bidirectional"))
    )
    (net (code "134") (name "unconnected-(MEGA2-20(SDA)-Pad20)") (class "Default")
      (node (ref "MEGA2") (pin "20") (pinfunction "20(SDA)_20") (pintype "bidirectional"))
    )
    (net (code "135") (name "unconnected-(MEGA2-21(SCL)-Pad21)") (class "Default")
      (node (ref "MEGA2") (pin "21") (pinfunction "21(SCL)_21") (pintype "bidirectional"))
    )
    (net (code "136") (name "unconnected-(MEGA2-IOREF-PadI{slash}OREF)") (class "Default")
      (node (ref "MEGA2") (pin "I/OREF") (pinfunction "IOREF_I/OREF") (pintype "bidirectional"))
    )
    (net (code "137") (name "unconnected-(MEGA2-Pad+5V_)") (class "Default")
      (node (ref "MEGA2") (pin "+5V_") (pinfunction "+5V__+5V_") (pintype "bidirectional"))
    )
    (net (code "138") (name "unconnected-(MEGA2-Pad3.3V)") (class "Default")
      (node (ref "MEGA2") (pin "3.3V") (pinfunction "3.3V_3.3V") (pintype "bidirectional"))
    )
    (net (code "139") (name "unconnected-(MEGA2-Pad5V)") (class "Default")
      (node (ref "MEGA2") (pin "5V") (pinfunction "5V_5V") (pintype "bidirectional"))
    )
    (net (code "140") (name "unconnected-(MEGA2-Pad22)") (class "Default")
      (node (ref "MEGA2") (pin "22") (pinfunction "22_22") (pintype "bidirectional"))
    )
    (net (code "141") (name "unconnected-(MEGA2-Pad23)") (class "Default")
      (node (ref "MEGA2") (pin "23") (pinfunction "23_23") (pintype "bidirectional"))
    )
    (net (code "142") (name "unconnected-(MEGA2-Pad24)") (class "Default")
      (node (ref "MEGA2") (pin "24") (pinfunction "24_24") (pintype "bidirectional"))
    )
    (net (code "143") (name "unconnected-(MEGA2-Pad25)") (class "Default")
      (node (ref "MEGA2") (pin "25") (pinfunction "25_25") (pintype "bidirectional"))
    )
    (net (code "144") (name "unconnected-(MEGA2-Pad26)") (class "Default")
      (node (ref "MEGA2") (pin "26") (pinfunction "26_26") (pintype "bidirectional"))
    )
    (net (code "145") (name "unconnected-(MEGA2-Pad27)") (class "Default")
      (node (ref "MEGA2") (pin "27") (pinfunction "27_27") (pintype "bidirectional"))
    )
    (net (code "146") (name "unconnected-(MEGA2-Pad28)") (class "Default")
      (node (ref "MEGA2") (pin "28") (pinfunction "28_28") (pintype "bidirectional"))
    )
    (net (code "147") (name "unconnected-(MEGA2-Pad29)") (class "Default")
      (node (ref "MEGA2") (pin "29") (pinfunction "29_29") (pintype "bidirectional"))
    )
    (net (code "148") (name "unconnected-(MEGA2-Pad30)") (class "Default")
      (node (ref "MEGA2") (pin "30") (pinfunction "30_30") (pintype "bidirectional"))
    )
    (net (code "149") (name "unconnected-(MEGA2-Pad31)") (class "Default")
      (node (ref "MEGA2") (pin "31") (pinfunction "31_31") (pintype "bidirectional"))
    )
    (net (code "150") (name "unconnected-(MEGA2-Pad32)") (class "Default")
      (node (ref "MEGA2") (pin "32") (pinfunction "32_32") (pintype "bidirectional"))
    )
    (net (code "151") (name "unconnected-(MEGA2-Pad33)") (class "Default")
      (node (ref "MEGA2") (pin "33") (pinfunction "33_33") (pintype "bidirectional"))
    )
    (net (code "152") (name "unconnected-(MEGA2-Pad34)") (class "Default")
      (node (ref "MEGA2") (pin "34") (pinfunction "34_34") (pintype "bidirectional"))
    )
    (net (code "153") (name "unconnected-(MEGA2-Pad35)") (class "Default")
      (node (ref "MEGA2") (pin "35") (pinfunction "35_35") (pintype "bidirectional"))
    )
    (net (code "154") (name "unconnected-(MEGA2-Pad36)") (class "Default")
      (node (ref "MEGA2") (pin "36") (pinfunction "36_36") (pintype "bidirectional"))
    )
    (net (code "155") (name "unconnected-(MEGA2-Pad37)") (class "Default")
      (node (ref "MEGA2") (pin "37") (pinfunction "37_37") (pintype "bidirectional"))
    )
    (net (code "156") (name "unconnected-(MEGA2-Pad38)") (class "Default")
      (node (ref "MEGA2") (pin "38") (pinfunction "38_38") (pintype "bidirectional"))
    )
    (net (code "157") (name "unconnected-(MEGA2-Pad39)") (class "Default")
      (node (ref "MEGA2") (pin "39") (pinfunction "39_39") (pintype "bidirectional"))
    )
    (net (code "158") (name "unconnected-(MEGA2-Pad40)") (class "Default")
      (node (ref "MEGA2") (pin "40") (pinfunction "40_40") (pintype "bidirectional"))
    )
    (net (code "159") (name "unconnected-(MEGA2-Pad41)") (class "Default")
      (node (ref "MEGA2") (pin "41") (pinfunction "41_41") (pintype "bidirectional"))
    )
    (net (code "160") (name "unconnected-(MEGA2-Pad42)") (class "Default")
      (node (ref "MEGA2") (pin "42") (pinfunction "42_42") (pintype "bidirectional"))
    )
    (net (code "161") (name "unconnected-(MEGA2-Pad43)") (class "Default")
      (node (ref "MEGA2") (pin "43") (pinfunction "43_43") (pintype "bidirectional"))
    )
    (net (code "162") (name "unconnected-(MEGA2-Pad44)") (class "Default")
      (node (ref "MEGA2") (pin "44") (pinfunction "44_44") (pintype "bidirectional"))
    )
    (net (code "163") (name "unconnected-(MEGA2-Pad45)") (class "Default")
      (node (ref "MEGA2") (pin "45") (pinfunction "45_45") (pintype "bidirectional"))
    )
    (net (code "164") (name "unconnected-(MEGA2-Pad46)") (class "Default")
      (node (ref "MEGA2") (pin "46") (pinfunction "46_46") (pintype "bidirectional"))
    )
    (net (code "165") (name "unconnected-(MEGA2-Pad47)") (class "Default")
      (node (ref "MEGA2") (pin "47") (pinfunction "47_47") (pintype "bidirectional"))
    )
    (net (code "166") (name "unconnected-(MEGA2-Pad48)") (class "Default")
      (node (ref "MEGA2") (pin "48") (pinfunction "48_48") (pintype "bidirectional"))
    )
    (net (code "167") (name "unconnected-(MEGA2-Pad49)") (class "Default")
      (node (ref "MEGA2") (pin "49") (pinfunction "49_49") (pintype "bidirectional"))
    )
    (net (code "168") (name "unconnected-(MEGA2-Pad50)") (class "Default")
      (node (ref "MEGA2") (pin "50") (pinfunction "50_50") (pintype "bidirectional"))
    )
    (net (code "169") (name "unconnected-(MEGA2-Pad51)") (class "Default")
      (node (ref "MEGA2") (pin "51") (pinfunction "51_51") (pintype "bidirectional"))
    )
    (net (code "170") (name "unconnected-(MEGA2-Pad52)") (class "Default")
      (node (ref "MEGA2") (pin "52") (pinfunction "52_52") (pintype "bidirectional"))
    )
    (net (code "171") (name "unconnected-(MEGA2-Pad53)") (class "Default")
      (node (ref "MEGA2") (pin "53") (pinfunction "53_53") (pintype "bidirectional"))
    )
    (net (code "172") (name "unconnected-(MEGA2-Pad<PWR>+V)") (class "Default")
      (node (ref "MEGA2") (pin "<PWR>+V") (pinfunction "<PWR>+V_<PWR>+V") (pintype "no_connect"))
    )
    (net (code "173") (name "unconnected-(MEGA2-Pad<PWR>-V)") (class "Default")
      (node (ref "MEGA2") (pin "<PWR>-V") (pinfunction "<PWR>-V_<PWR>-V") (pintype "no_connect"))
    )
    (net (code "174") (name "unconnected-(MEGA2-Pad<USB>+V)") (class "Default")
      (node (ref "MEGA2") (pin "<USB>+V") (pinfunction "<USB>+V_<USB>+V") (pintype "no_connect"))
    )
    (net (code "175") (name "unconnected-(MEGA2-Pad<USB>D+)") (class "Default")
      (node (ref "MEGA2") (pin "<USB>D+") (pinfunction "<USB>D+_<USB>D+") (pintype "no_connect"))
    )
    (net (code "176") (name "unconnected-(MEGA2-Pad<USB>D-)") (class "Default")
      (node (ref "MEGA2") (pin "<USB>D-") (pinfunction "<USB>D-_<USB>D-") (pintype "no_connect"))
    )
    (net (code "177") (name "unconnected-(MEGA2-Pad<USB>GND)") (class "Default")
      (node (ref "MEGA2") (pin "<USB>GND") (pinfunction "<USB>GND_<USB>GND") (pintype "no_connect"))
    )
    (net (code "178") (name "unconnected-(MEGA2-PadA0)") (class "Default")
      (node (ref "MEGA2") (pin "A0") (pinfunction "A0_A0") (pintype "bidirectional"))
    )
    (net (code "179") (name "unconnected-(MEGA2-PadA1)") (class "Default")
      (node (ref "MEGA2") (pin "A1") (pinfunction "A1_A1") (pintype "bidirectional"))
    )
    (net (code "180") (name "unconnected-(MEGA2-PadA2)") (class "Default")
      (node (ref "MEGA2") (pin "A2") (pinfunction "A2_A2") (pintype "bidirectional"))
    )
    (net (code "181") (name "unconnected-(MEGA2-PadA3)") (class "Default")
      (node (ref "MEGA2") (pin "A3") (pinfunction "A3_A3") (pintype "bidirectional"))
    )
    (net (code "182") (name "unconnected-(MEGA2-PadA4)") (class "Default")
      (node (ref "MEGA2") (pin "A4") (pinfunction "A4_A4") (pintype "bidirectional"))
    )
    (net (code "183") (name "unconnected-(MEGA2-PadA5)") (class "Default")
      (node (ref "MEGA2") (pin "A5") (pinfunction "A5_A5") (pintype "bidirectional"))
    )
    (net (code "184") (name "unconnected-(MEGA2-PadA6)") (class "Default")
      (node (ref "MEGA2") (pin "A6") (pinfunction "A6_A6") (pintype "bidirectional"))
    )
    (net (code "185") (name "unconnected-(MEGA2-PadA7)") (class "Default")
      (node (ref "MEGA2") (pin "A7") (pinfunction "A7_A7") (pintype "bidirectional"))
    )
    (net (code "186") (name "unconnected-(MEGA2-PadA8)") (class "Default")
      (node (ref "MEGA2") (pin "A8") (pinfunction "A8_A8") (pintype "bidirectional"))
    )
    (net (code "187") (name "unconnected-(MEGA2-PadA9)") (class "Default")
      (node (ref "MEGA2") (pin "A9") (pinfunction "A9_A9") (pintype "bidirectional"))
    )
    (net (code "188") (name "unconnected-(MEGA2-PadA10)") (class "Default")
      (node (ref "MEGA2") (pin "A10") (pinfunction "A10_A10") (pintype "bidirectional"))
    )
    (net (code "189") (name "unconnected-(MEGA2-PadA11)") (class "Default")
      (node (ref "MEGA2") (pin "A11") (pinfunction "A11_A11") (pintype "bidirectional"))
    )
    (net (code "190") (name "unconnected-(MEGA2-PadA12)") (class "Default")
      (node (ref "MEGA2") (pin "A12") (pinfunction "A12_A12") (pintype "bidirectional"))
    )
    (net (code "191") (name "unconnected-(MEGA2-PadA13)") (class "Default")
      (node (ref "MEGA2") (pin "A13") (pinfunction "A13_A13") (pintype "bidirectional"))
    )
    (net (code "192") (name "unconnected-(MEGA2-PadA14)") (class "Default")
      (node (ref "MEGA2") (pin "A14") (pinfunction "A14_A14") (pintype "bidirectional"))
    )
    (net (code "193") (name "unconnected-(MEGA2-PadA15)") (class "Default")
      (node (ref "MEGA2") (pin "A15") (pinfunction "A15_A15") (pintype "bidirectional"))
    )
    (net (code "194") (name "unconnected-(MEGA2-PadAREF)") (class "Default")
      (node (ref "MEGA2") (pin "AREF") (pinfunction "AREF_AREF") (pintype "bidirectional"))
    )
    (net (code "195") (name "unconnected-(MEGA2-PadGND)") (class "Default")
      (node (ref "MEGA2") (pin "GND") (pinfunction "GND_GND") (pintype "bidirectional"))
    )
    (net (code "196") (name "unconnected-(MEGA2-PadGND...)") (class "Default")
      (node (ref "MEGA2") (pin "GND...") (pinfunction "GND..._GND...") (pintype "bidirectional"))
    )
    (net (code "197") (name "unconnected-(MEGA2-PadGND....)") (class "Default")
      (node (ref "MEGA2") (pin "GND....") (pinfunction "GND...._GND....") (pintype "bidirectional"))
    )
    (net (code "198") (name "unconnected-(MEGA2-PadGND__)") (class "Default")
      (node (ref "MEGA2") (pin "GND__") (pinfunction "GND___GND__") (pintype "bidirectional"))
    )
    (net (code "199") (name "unconnected-(MEGA2-PadMISO)") (class "Default")
      (node (ref "MEGA2") (pin "MISO") (pinfunction "MISO_MISO") (pintype "bidirectional"))
    )
    (net (code "200") (name "unconnected-(MEGA2-PadMOSI)") (class "Default")
      (node (ref "MEGA2") (pin "MOSI") (pinfunction "MOSI_MOSI") (pintype "bidirectional"))
    )
    (net (code "201") (name "unconnected-(MEGA2-PadRESET)") (class "Default")
      (node (ref "MEGA2") (pin "RESET") (pinfunction "RESET_RESET") (pintype "bidirectional"))
    )
    (net (code "202") (name "unconnected-(MEGA2-PadRESET.)") (class "Default")
      (node (ref "MEGA2") (pin "RESET.") (pinfunction "RESET._RESET.") (pintype "bidirectional"))
    )
    (net (code "203") (name "unconnected-(MEGA2-PadSCK)") (class "Default")
      (node (ref "MEGA2") (pin "SCK") (pinfunction "SCK_SCK") (pintype "bidirectional"))
    )
    (net (code "204") (name "unconnected-(MEGA2-PadSCL1)") (class "Default")
      (node (ref "MEGA2") (pin "SCL1") (pinfunction "SCL1_SCL1") (pintype "bidirectional"))
    )
    (net (code "205") (name "unconnected-(MEGA2-PadSDA1)") (class "Default")
      (node (ref "MEGA2") (pin "SDA1") (pinfunction "SDA1_SDA1") (pintype "bidirectional"))
    )
    (net (code "206") (name "unconnected-(X7A-KL-Pad1)") (class "Default")
      (node (ref "X7") (pin "1") (pinfunction "KL_1") (pintype "passive"))
    )
  )
)
